# VREG_RT9166-28PVL.net
KiCad netlist of a schematic drawn in Altium Designer
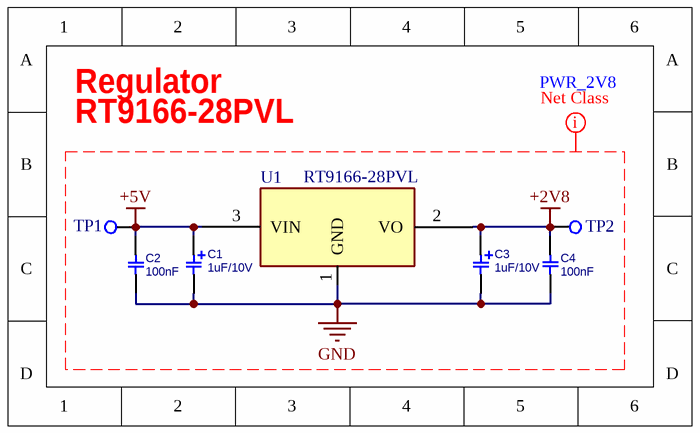
[diagram p0: VREG RT9166-28PVL.SchDoc]

(export (version "E")
  (design (tool "Eeschema 10.0.6"))
  (components
    (comp (ref "C1")
      (value "1uF/10V")
      (footprint "C_TN_A")
      (description "CAP, SMD, TAN")
      (libsource (lib "PW Components 97_492") (part "CAP_SMD_TAN"))
    )
    (comp (ref "C2")
      (value "100nF")
      (footprint "C0603S")
      (description "CAP, SMD, MLCC")
      (fields (field (name "MANF_P#") "MANF_PART#") (field (name "MANF") "Murata"))
      (libsource (lib "Passive") (part "CAP_SMD_MLCC"))
    )
    (comp (ref "C3")
      (value "1uF/10V")
      (footprint "C_TN_A")
      (description "CAP, SMD, TAN")
      (libsource (lib "PW Components 97_492") (part "CAP_SMD_TAN"))
    )
    (comp (ref "C4")
      (value "100nF")
      (footprint "C0603S")
      (description "CAP, SMD, MLCC")
      (fields (field (name "MANF_P#") "MANF_PART#") (field (name "MANF") "Murata"))
      (libsource (lib "Passive") (part "CAP_SMD_MLCC"))
    )
    (comp (ref "TP1")
      (value "Test Point")
      (footprint "TPSMD_C1")
      (libsource (lib "Passives") (part "Test Point"))
    )
    (comp (ref "TP2")
      (value "Test Point")
      (footprint "TPSMD_C1")
      (libsource (lib "Passives") (part "Test Point"))
    )
    (comp (ref "U1")
      (value "RT9166-28PVL")
      (footprint "SOT23_3")
      (description "REG, Linear, Fixed, 2.8v, 0.3A/0.6A, SOT23")
      (fields (field (name "MANF") "TI"))
      (libsource (lib "PW Components 97_481") (part "VREG_RT9166A-28PVL_SOT23"))
    )
  )
  (nets
    (net (code "1") (name "+2V8") (class "Default")
      (node (ref "C3") (pin "1") (pinfunction "1_1") (pintype "passive"))
      (node (ref "C4") (pin "1") (pinfunction "1_1") (pintype "passive"))
      (node (ref "TP2") (pin "1") (pinfunction "TP_1") (pintype "passive"))
      (node (ref "U1") (pin "2") (pinfunction "VO_2") (pintype "passive"))
    )
    (net (code "2") (name "+5V") (class "Default")
      (node (ref "C1") (pin "1") (pinfunction "1_1") (pintype "passive"))
      (node (ref "C2") (pin "1") (pinfunction "1_1") (pintype "passive"))
      (node (ref "TP1") (pin "1") (pinfunction "TP_1") (pintype "passive"))
      (node (ref "U1") (pin "3") (pinfunction "VIN_3") (pintype "passive"))
    )
    (net (code "3") (name "GND") (class "Default")
      (node (ref "C1") (pin "2") (pinfunction "2_2") (pintype "passive"))
      (node (ref "C2") (pin "2") (pinfunction "2_2") (pintype "passive"))
      (node (ref "C3") (pin "2") (pinfunction "2_2") (pintype "passive"))
      (node (ref "C4") (pin "2") (pinfunction "2_2") (pintype "passive"))
      (node (ref "U1") (pin "1") (pinfunction "GND_1") (pintype "passive"))
    )
  )
)
